# zasilanie.net
KiCad netlist of a schematic drawn in EAGLE
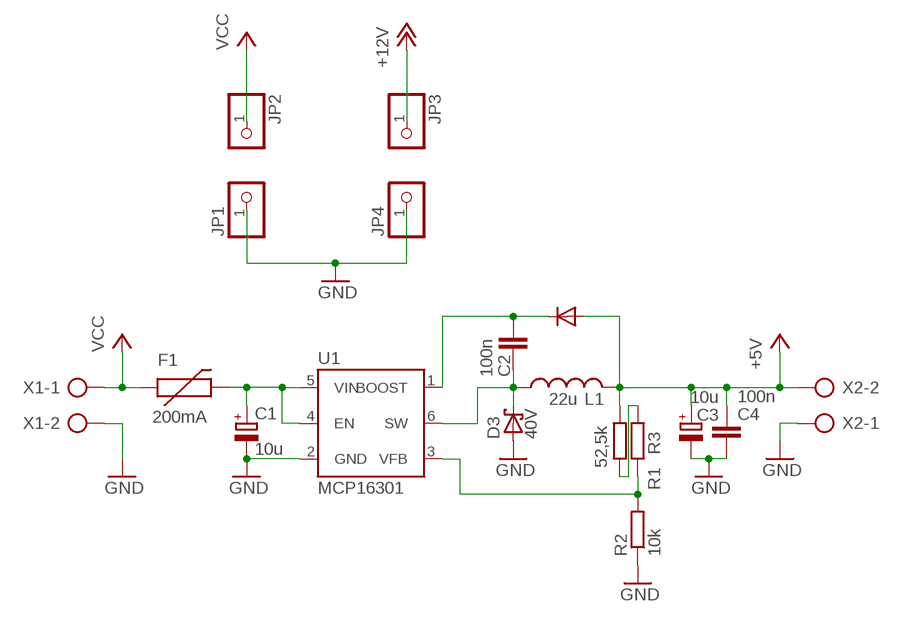
[diagram p0: schematic, sheet 1]

(export (version "E")
  (design (tool "Eeschema 10.0.6"))
  (components
    (comp (ref "C1")
      (value "10u")
      (footprint "eagle-import:PANASONIC_F")
      (libsource (lib "eagle-import") (part "CPOL-EUF"))
    )
    (comp (ref "C2")
      (value "100n")
      (footprint "eagle-import:C0805")
      (libsource (lib "eagle-import") (part "C-EUC0805"))
    )
    (comp (ref "C3")
      (value "10u")
      (footprint "eagle-import:PANASONIC_F")
      (libsource (lib "eagle-import") (part "CPOL-EUF"))
    )
    (comp (ref "C4")
      (value "100n")
      (footprint "eagle-import:C0805")
      (libsource (lib "eagle-import") (part "C-EUC0805"))
    )
    (comp (ref "D1")
      (value "DIODE-SMC")
      (footprint "eagle-import:SMC")
      (libsource (lib "eagle-import") (part "DIODE-SMC"))
    )
    (comp (ref "D3")
      (value "40V")
      (footprint "eagle-import:SMC")
      (libsource (lib "eagle-import") (part "SCHOTTKY-DIODESMC"))
    )
    (comp (ref "F1")
      (value "200mA")
      (footprint "eagle-import:PTC-1206")
      (libsource (lib "eagle-import") (part "PTCSMD"))
    )
    (comp (ref "JP1")
      (value "PINHD-1X1")
      (footprint "eagle-import:1X01")
      (libsource (lib "eagle-import") (part "PINHD-1X1"))
    )
    (comp (ref "JP2")
      (value "PINHD-1X1")
      (footprint "eagle-import:1X01")
      (libsource (lib "eagle-import") (part "PINHD-1X1"))
    )
    (comp (ref "JP3")
      (value "PINHD-1X1")
      (footprint "eagle-import:1X01")
      (libsource (lib "eagle-import") (part "PINHD-1X1"))
    )
    (comp (ref "JP4")
      (value "PINHD-1X1")
      (footprint "eagle-import:1X01")
      (libsource (lib "eagle-import") (part "PINHD-1X1"))
    )
    (comp (ref "L1")
      (value "22u")
      (footprint "eagle-import:CDRH125")
      (libsource (lib "eagle-import") (part "INDUCTORPWR"))
    )
    (comp (ref "R1")
      (value "52,5k")
      (footprint "eagle-import:R0805")
      (libsource (lib "eagle-import") (part "R-EU_R0805"))
    )
    (comp (ref "R2")
      (value "10k")
      (footprint "eagle-import:R0805")
      (libsource (lib "eagle-import") (part "R-EU_R0805"))
    )
    (comp (ref "R3")
      (value "R-EU_R0805")
      (footprint "eagle-import:R0805")
      (libsource (lib "eagle-import") (part "R-EU_R0805"))
    )
    (comp (ref "U1")
      (value "MCP16301")
      (footprint "eagle-import:SOT23-6")
      (libsource (lib "eagle-import") (part "MCP4725SOT-23"))
    )
    (comp (ref "X1")
      (value "AK500/2")
      (footprint "eagle-import:AK500_2")
      (libsource (lib "eagle-import") (part "AK500/2"))
    )
    (comp (ref "X2")
      (value "AK500/2")
      (footprint "eagle-import:AK500_2")
      (libsource (lib "eagle-import") (part "AK500/2"))
    )
  )
  (nets
    (net (code "1") (name "+5V") (class "Default")
      (node (ref "C3") (pin "+") (pinfunction "+_+") (pintype "passive"))
      (node (ref "C4") (pin "1") (pinfunction "1_1") (pintype "passive"))
      (node (ref "D1") (pin "A") (pinfunction "A_A") (pintype "passive"))
      (node (ref "L1") (pin "2") (pinfunction "2_2") (pintype "passive"))
      (node (ref "R1") (pin "2") (pinfunction "2_2") (pintype "passive"))
      (node (ref "X2") (pin "2") (pinfunction "KL_2") (pintype "passive"))
    )
    (net (code "2") (name "+12V") (class "Default")
      (node (ref "JP3") (pin "1") (pinfunction "1_1") (pintype "passive"))
    )
    (net (code "3") (name "GND") (class "Default")
      (node (ref "C1") (pin "-") (pinfunction "-_-") (pintype "passive"))
      (node (ref "C3") (pin "-") (pinfunction "-_-") (pintype "passive"))
      (node (ref "C4") (pin "2") (pinfunction "2_2") (pintype "passive"))
      (node (ref "D3") (pin "A") (pinfunction "A_A") (pintype "passive"))
      (node (ref "JP1") (pin "1") (pinfunction "1_1") (pintype "passive"))
      (node (ref "JP4") (pin "1") (pinfunction "1_1") (pintype "passive"))
      (node (ref "R2") (pin "1") (pinfunction "1_1") (pintype "passive"))
      (node (ref "U1") (pin "2") (pinfunction "GND_2") (pintype "bidirectional"))
      (node (ref "X1") (pin "2") (pinfunction "KL_2") (pintype "passive"))
      (node (ref "X2") (pin "1") (pinfunction "KL_1") (pintype "passive"))
    )
    (net (code "4") (name "Net-(R1-Pad1)") (class "Default")
      (node (ref "R1") (pin "1") (pinfunction "1_1") (pintype "passive"))
      (node (ref "R3") (pin "2") (pinfunction "2_2") (pintype "passive"))
    )
    (net (code "5") (name "Net-(U1-BOOST)") (class "Default")
      (node (ref "C2") (pin "1") (pinfunction "1_1") (pintype "passive"))
      (node (ref "D1") (pin "C") (pinfunction "C_C") (pintype "passive"))
      (node (ref "U1") (pin "1") (pinfunction "BOOST_1") (pintype "bidirectional"))
    )
    (net (code "6") (name "Net-(U1-EN)") (class "Default")
      (node (ref "C1") (pin "+") (pinfunction "+_+") (pintype "passive"))
      (node (ref "F1") (pin "2") (pinfunction "2_2") (pintype "bidirectional"))
      (node (ref "U1") (pin "4") (pinfunction "EN_4") (pintype "bidirectional"))
      (node (ref "U1") (pin "5") (pinfunction "VIN_5") (pintype "bidirectional"))
    )
    (net (code "7") (name "Net-(U1-SW)") (class "Default")
      (node (ref "C2") (pin "2") (pinfunction "2_2") (pintype "passive"))
      (node (ref "D3") (pin "C") (pinfunction "C_C") (pintype "passive"))
      (node (ref "L1") (pin "1") (pinfunction "1_1") (pintype "passive"))
      (node (ref "U1") (pin "6") (pinfunction "SW_6") (pintype "bidirectional"))
    )
    (net (code "8") (name "Net-(U1-VFB)") (class "Default")
      (node (ref "R2") (pin "2") (pinfunction "2_2") (pintype "passive"))
      (node (ref "R3") (pin "1") (pinfunction "1_1") (pintype "passive"))
      (node (ref "U1") (pin "3") (pinfunction "VFB_3") (pintype "bidirectional"))
    )
    (net (code "9") (name "VCC") (class "Default")
      (node (ref "F1") (pin "1") (pinfunction "1_1") (pintype "bidirectional"))
      (node (ref "JP2") (pin "1") (pinfunction "1_1") (pintype "passive"))
      (node (ref "X1") (pin "1") (pinfunction "KL_1") (pintype "passive"))
    )
  )
)
